# Guitar-Controller.net
KiCad netlist of a schematic drawn in EAGLE
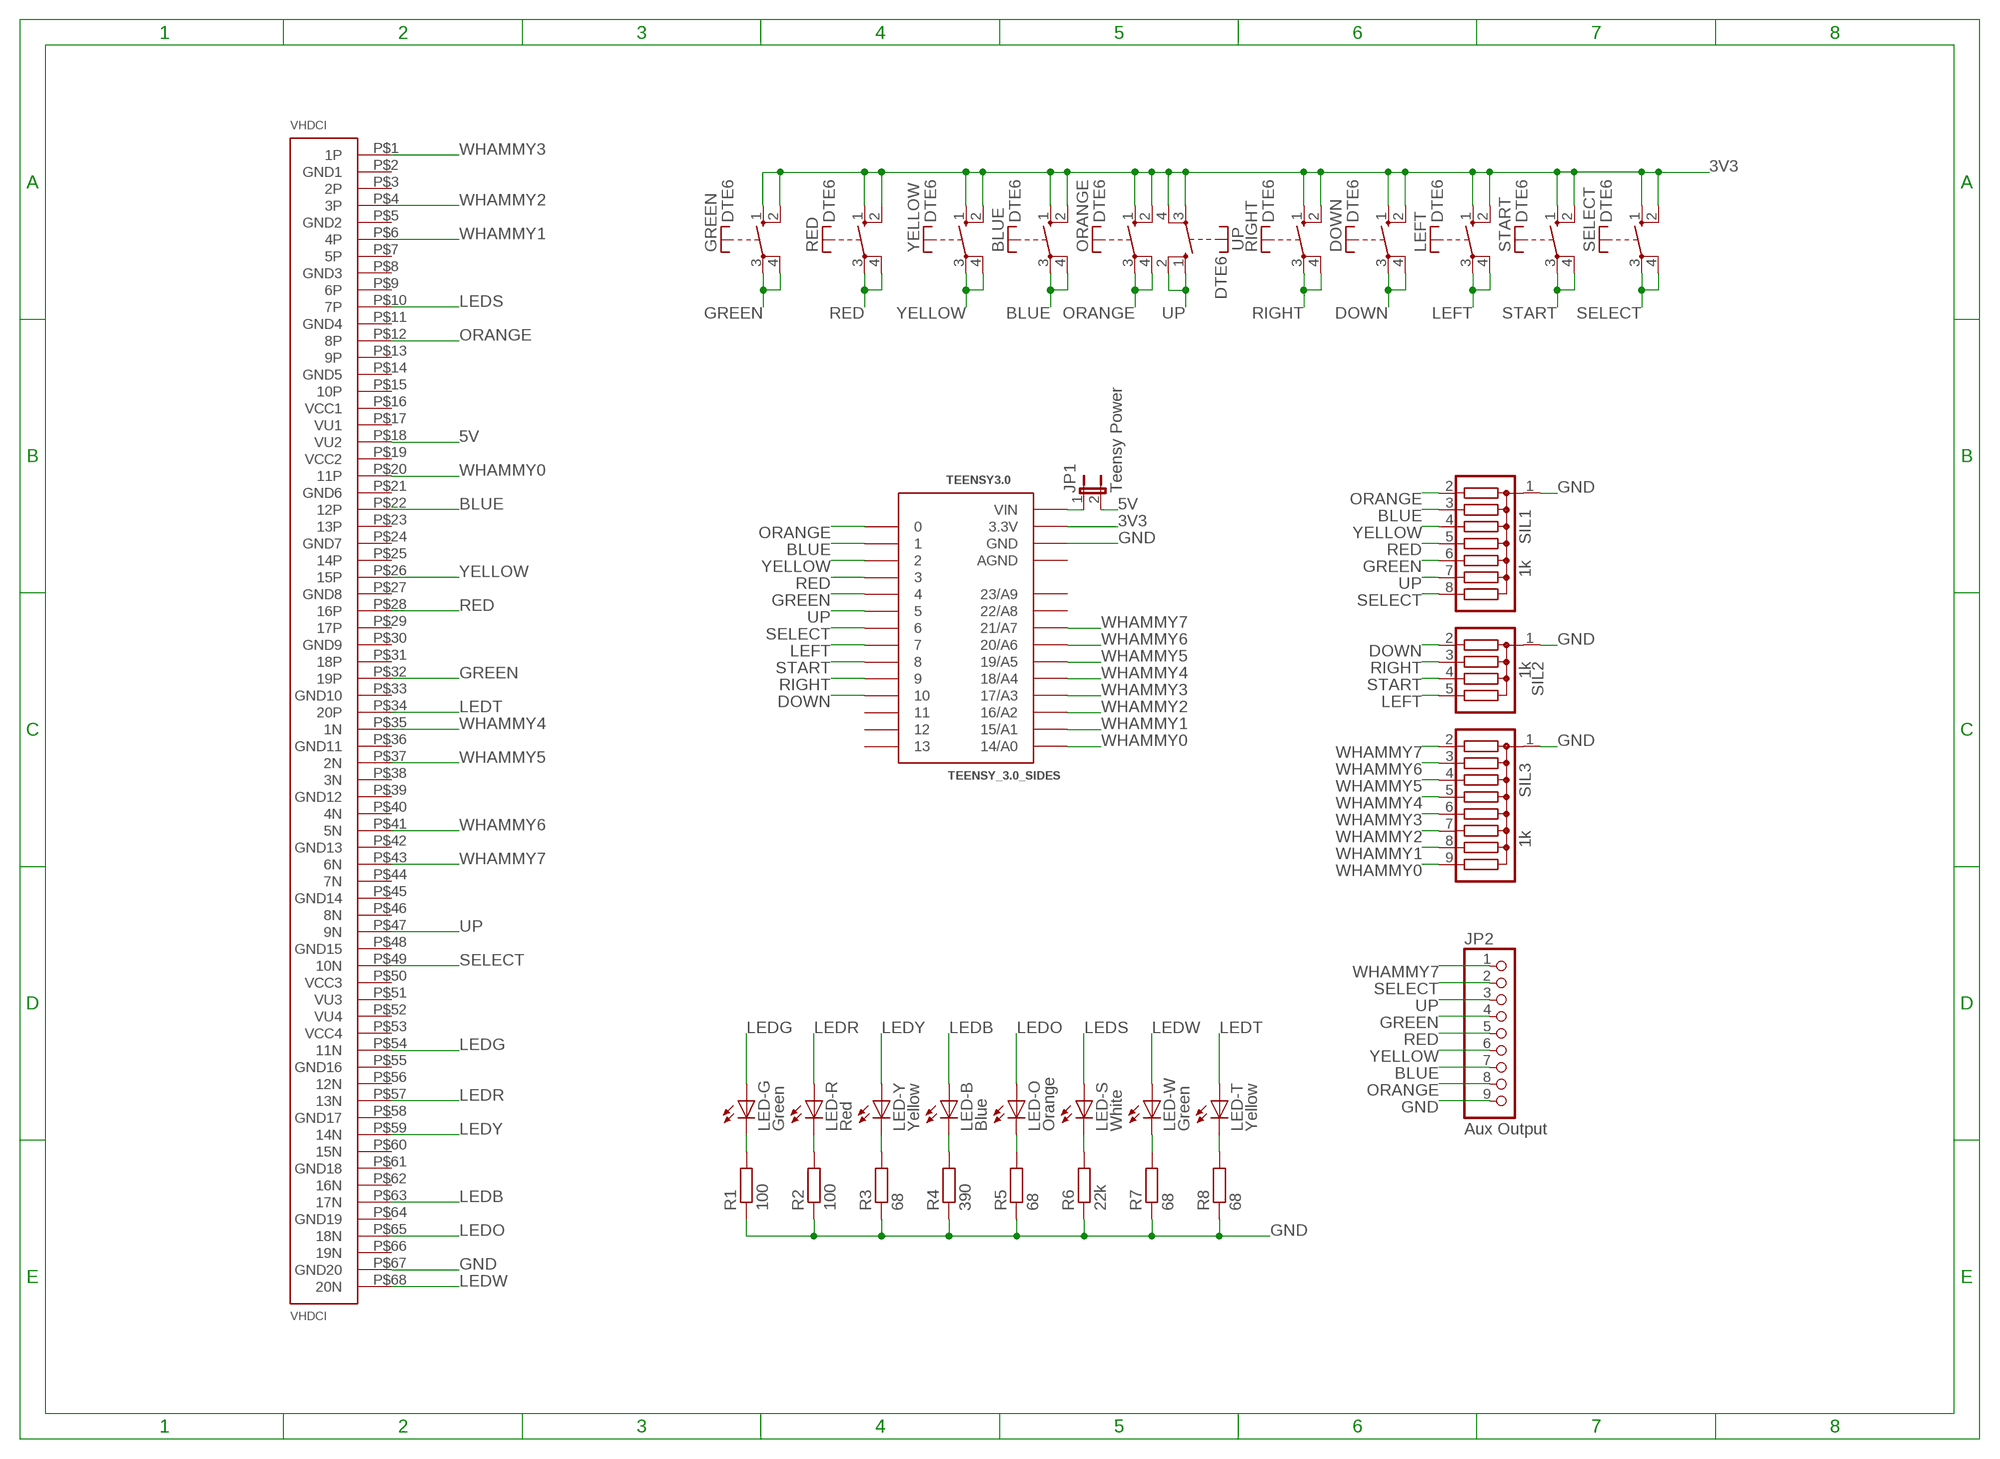
[diagram p0: schematic, sheet 1]

(export (version "E")
  (design (tool "Eeschema 10.0.6"))
  (components
    (comp (ref "BLUE")
      (value "DTE6")
      (footprint "eagle-import:DTE6")
      (libsource (lib "eagle-import") (part "DTE6"))
    )
    (comp (ref "DOWN")
      (value "DTE6")
      (footprint "eagle-import:DTE6")
      (libsource (lib "eagle-import") (part "DTE6"))
    )
    (comp (ref "GREEN")
      (value "DTE6")
      (footprint "eagle-import:DTE6")
      (libsource (lib "eagle-import") (part "DTE6"))
    )
    (comp (ref "JP1")
      (value "Teensy Power")
      (footprint "eagle-import:JP1")
      (libsource (lib "eagle-import") (part "JP1E"))
    )
    (comp (ref "JP2")
      (value "Aux Output")
      (footprint "eagle-import:1X09_90")
      (libsource (lib "eagle-import") (part "PINHD-1X9/90"))
    )
    (comp (ref "LED-B")
      (value "Blue")
      (footprint "eagle-import:LED2X5")
      (libsource (lib "eagle-import") (part "LEDSQR2X5"))
    )
    (comp (ref "LED-G")
      (value "Green")
      (footprint "eagle-import:LED2X5")
      (libsource (lib "eagle-import") (part "LEDSQR2X5"))
    )
    (comp (ref "LED-O")
      (value "Orange")
      (footprint "eagle-import:LED2X5")
      (libsource (lib "eagle-import") (part "LEDSQR2X5"))
    )
    (comp (ref "LED-R")
      (value "Red")
      (footprint "eagle-import:LED2X5")
      (libsource (lib "eagle-import") (part "LEDSQR2X5"))
    )
    (comp (ref "LED-S")
      (value "White")
      (footprint "eagle-import:LED5MM")
      (libsource (lib "eagle-import") (part "LED5MM"))
    )
    (comp (ref "LED-T")
      (value "Yellow")
      (footprint "eagle-import:LED3MM")
      (libsource (lib "eagle-import") (part "LED3MM"))
    )
    (comp (ref "LED-W")
      (value "Green")
      (footprint "eagle-import:LED3MM")
      (libsource (lib "eagle-import") (part "LED3MM"))
    )
    (comp (ref "LED-Y")
      (value "Yellow")
      (footprint "eagle-import:LED2X5")
      (libsource (lib "eagle-import") (part "LEDSQR2X5"))
    )
    (comp (ref "LEFT")
      (value "DTE6")
      (footprint "eagle-import:DTE6")
      (libsource (lib "eagle-import") (part "DTE6"))
    )
    (comp (ref "ORANGE")
      (value "DTE6")
      (footprint "eagle-import:DTE6")
      (libsource (lib "eagle-import") (part "DTE6"))
    )
    (comp (ref "R1")
      (value "100")
      (footprint "eagle-import:R0805")
      (libsource (lib "eagle-import") (part "R-EU_R0805"))
    )
    (comp (ref "R2")
      (value "100")
      (footprint "eagle-import:R0805")
      (libsource (lib "eagle-import") (part "R-EU_R0805"))
    )
    (comp (ref "R3")
      (value "68")
      (footprint "eagle-import:R0805")
      (libsource (lib "eagle-import") (part "R-EU_R0805"))
    )
    (comp (ref "R4")
      (value "390")
      (footprint "eagle-import:R0805")
      (libsource (lib "eagle-import") (part "R-EU_R0805"))
    )
    (comp (ref "R5")
      (value "68")
      (footprint "eagle-import:R0805")
      (libsource (lib "eagle-import") (part "R-EU_R0805"))
    )
    (comp (ref "R6")
      (value "22k")
      (footprint "eagle-import:R0805")
      (libsource (lib "eagle-import") (part "R-EU_R0805"))
    )
    (comp (ref "R7")
      (value "68")
      (footprint "eagle-import:R0805")
      (libsource (lib "eagle-import") (part "R-EU_R0805"))
    )
    (comp (ref "R8")
      (value "68")
      (footprint "eagle-import:R0805")
      (libsource (lib "eagle-import") (part "R-EU_R0805"))
    )
    (comp (ref "RED")
      (value "DTE6")
      (footprint "eagle-import:DTE6")
      (libsource (lib "eagle-import") (part "DTE6"))
    )
    (comp (ref "RIGHT")
      (value "DTE6")
      (footprint "eagle-import:DTE6")
      (libsource (lib "eagle-import") (part "DTE6"))
    )
    (comp (ref "SELECT")
      (value "DTE6")
      (footprint "eagle-import:DTE6")
      (libsource (lib "eagle-import") (part "DTE6"))
    )
    (comp (ref "SIL1")
      (value "1k")
      (footprint "eagle-import:SIL8")
      (libsource (lib "eagle-import") (part "G07R"))
    )
    (comp (ref "SIL2")
      (value "1k")
      (footprint "eagle-import:SIL5")
      (fields (field (name "OC_FARNELL") "unknown") (field (name "OC_NEWARK") "unknown"))
      (libsource (lib "eagle-import") (part "G04R"))
    )
    (comp (ref "SIL3")
      (value "1k")
      (footprint "eagle-import:SIL9")
      (libsource (lib "eagle-import") (part "G08R"))
    )
    (comp (ref "START")
      (value "DTE6")
      (footprint "eagle-import:DTE6")
      (libsource (lib "eagle-import") (part "DTE6"))
    )
    (comp (ref "TEENSY3.0")
      (value "TEENSY_3.0_SIDES")
      (footprint "eagle-import:TEENSY_3.0_SIDES")
      (libsource (lib "eagle-import") (part "TEENSY_3.0_SIDES"))
    )
    (comp (ref "UP")
      (value "DTE6")
      (footprint "eagle-import:DTE6")
      (libsource (lib "eagle-import") (part "DTE6"))
    )
    (comp (ref "VHDCI")
      (value "VHDCI-PLUG")
      (footprint "eagle-import:R-HI-008068-2")
      (libsource (lib "eagle-import") (part "VHDCI-PLUG"))
    )
    (comp (ref "YELLOW")
      (value "DTE6")
      (footprint "eagle-import:DTE6")
      (libsource (lib "eagle-import") (part "DTE6"))
    )
  )
  (nets
    (net (code "1") (name "/3V3") (class "Default")
      (node (ref "BLUE") (pin "1") (pinfunction "S_1") (pintype "passive"))
      (node (ref "BLUE") (pin "2") (pinfunction "S_2") (pintype "passive"))
      (node (ref "DOWN") (pin "1") (pinfunction "S_1") (pintype "passive"))
      (node (ref "DOWN") (pin "2") (pinfunction "S_2") (pintype "passive"))
      (node (ref "GREEN") (pin "1") (pinfunction "S_1") (pintype "passive"))
      (node (ref "GREEN") (pin "2") (pinfunction "S_2") (pintype "passive"))
      (node (ref "LEFT") (pin "1") (pinfunction "S_1") (pintype "passive"))
      (node (ref "LEFT") (pin "2") (pinfunction "S_2") (pintype "passive"))
      (node (ref "ORANGE") (pin "1") (pinfunction "S_1") (pintype "passive"))
      (node (ref "ORANGE") (pin "2") (pinfunction "S_2") (pintype "passive"))
      (node (ref "RED") (pin "1") (pinfunction "S_1") (pintype "passive"))
      (node (ref "RED") (pin "2") (pinfunction "S_2") (pintype "passive"))
      (node (ref "RIGHT") (pin "1") (pinfunction "S_1") (pintype "passive"))
      (node (ref "RIGHT") (pin "2") (pinfunction "S_2") (pintype "passive"))
      (node (ref "SELECT") (pin "1") (pinfunction "S_1") (pintype "passive"))
      (node (ref "SELECT") (pin "2") (pinfunction "S_2") (pintype "passive"))
      (node (ref "START") (pin "1") (pinfunction "S_1") (pintype "passive"))
      (node (ref "START") (pin "2") (pinfunction "S_2") (pintype "passive"))
      (node (ref "TEENSY3.0") (pin "3.3V") (pinfunction "3.3V_3.3V") (pintype "power_in"))
      (node (ref "UP") (pin "3") (pinfunction "P_3") (pintype "passive"))
      (node (ref "UP") (pin "4") (pinfunction "P_4") (pintype "passive"))
      (node (ref "YELLOW") (pin "1") (pinfunction "S_1") (pintype "passive"))
      (node (ref "YELLOW") (pin "2") (pinfunction "S_2") (pintype "passive"))
    )
    (net (code "2") (name "/5V") (class "Default")
      (node (ref "JP1") (pin "2") (pinfunction "2_2") (pintype "passive"))
      (node (ref "VHDCI") (pin "P$18") (pinfunction "VU2_P$18") (pintype "bidirectional"))
    )
    (net (code "3") (name "/AGND") (class "Default")
      (node (ref "TEENSY3.0") (pin "AGND") (pinfunction "AGND_AGND") (pintype "power_in"))
    )
    (net (code "4") (name "/BLUE") (class "Default")
      (node (ref "BLUE") (pin "3") (pinfunction "P_3") (pintype "passive"))
      (node (ref "BLUE") (pin "4") (pinfunction "P_4") (pintype "passive"))
      (node (ref "JP2") (pin "7") (pinfunction "7_7") (pintype "passive"))
      (node (ref "SIL1") (pin "3") (pinfunction "3_3") (pintype "passive"))
      (node (ref "TEENSY3.0") (pin "1") (pinfunction "1_1") (pintype "bidirectional"))
      (node (ref "VHDCI") (pin "P$22") (pinfunction "12P_P$22") (pintype "bidirectional"))
    )
    (net (code "5") (name "/DOWN") (class "Default")
      (node (ref "DOWN") (pin "3") (pinfunction "P_3") (pintype "passive"))
      (node (ref "DOWN") (pin "4") (pinfunction "P_4") (pintype "passive"))
      (node (ref "SIL2") (pin "2") (pinfunction "2_2") (pintype "passive"))
      (node (ref "TEENSY3.0") (pin "10") (pinfunction "10_10") (pintype "bidirectional"))
    )
    (net (code "6") (name "/GND") (class "Default")
      (node (ref "JP2") (pin "9") (pinfunction "9_9") (pintype "passive"))
      (node (ref "R1") (pin "1") (pinfunction "1_1") (pintype "passive"))
      (node (ref "R2") (pin "1") (pinfunction "1_1") (pintype "passive"))
      (node (ref "R3") (pin "1") (pinfunction "1_1") (pintype "passive"))
      (node (ref "R4") (pin "1") (pinfunction "1_1") (pintype "passive"))
      (node (ref "R5") (pin "1") (pinfunction "1_1") (pintype "passive"))
      (node (ref "R6") (pin "1") (pinfunction "1_1") (pintype "passive"))
      (node (ref "R7") (pin "1") (pinfunction "1_1") (pintype "passive"))
      (node (ref "R8") (pin "1") (pinfunction "1_1") (pintype "passive"))
      (node (ref "SIL1") (pin "1") (pinfunction "1_1") (pintype "passive"))
      (node (ref "SIL2") (pin "1") (pinfunction "1_1") (pintype "passive"))
      (node (ref "SIL3") (pin "1") (pinfunction "1_1") (pintype "passive"))
      (node (ref "TEENSY3.0") (pin "GND") (pinfunction "GND_GND") (pintype "power_in"))
      (node (ref "VHDCI") (pin "P$67") (pinfunction "GND20_P$67") (pintype "bidirectional"))
    )
    (net (code "7") (name "/GREEN") (class "Default")
      (node (ref "GREEN") (pin "3") (pinfunction "P_3") (pintype "passive"))
      (node (ref "GREEN") (pin "4") (pinfunction "P_4") (pintype "passive"))
      (node (ref "JP2") (pin "4") (pinfunction "4_4") (pintype "passive"))
      (node (ref "SIL1") (pin "6") (pinfunction "6_6") (pintype "passive"))
      (node (ref "TEENSY3.0") (pin "4") (pinfunction "4_4") (pintype "bidirectional"))
      (node (ref "VHDCI") (pin "P$32") (pinfunction "19P_P$32") (pintype "bidirectional"))
    )
    (net (code "8") (name "/LEDB") (class "Default")
      (node (ref "LED-B") (pin "A") (pinfunction "A_A") (pintype "passive"))
      (node (ref "VHDCI") (pin "P$63") (pinfunction "17N_P$63") (pintype "bidirectional"))
    )
    (net (code "9") (name "/LEDG") (class "Default")
      (node (ref "LED-G") (pin "A") (pinfunction "A_A") (pintype "passive"))
      (node (ref "VHDCI") (pin "P$54") (pinfunction "11N_P$54") (pintype "bidirectional"))
    )
    (net (code "10") (name "/LEDO") (class "Default")
      (node (ref "LED-O") (pin "A") (pinfunction "A_A") (pintype "passive"))
      (node (ref "VHDCI") (pin "P$65") (pinfunction "18N_P$65") (pintype "bidirectional"))
    )
    (net (code "11") (name "/LEDR") (class "Default")
      (node (ref "LED-R") (pin "A") (pinfunction "A_A") (pintype "passive"))
      (node (ref "VHDCI") (pin "P$57") (pinfunction "13N_P$57") (pintype "bidirectional"))
    )
    (net (code "12") (name "/LEDS") (class "Default")
      (node (ref "LED-S") (pin "A") (pinfunction "A_A") (pintype "passive"))
      (node (ref "VHDCI") (pin "P$10") (pinfunction "7P_P$10") (pintype "bidirectional"))
    )
    (net (code "13") (name "/LEDT") (class "Default")
      (node (ref "LED-T") (pin "A") (pinfunction "A_A") (pintype "passive"))
      (node (ref "VHDCI") (pin "P$34") (pinfunction "20P_P$34") (pintype "bidirectional"))
    )
    (net (code "14") (name "/LEDW") (class "Default")
      (node (ref "LED-W") (pin "A") (pinfunction "A_A") (pintype "passive"))
      (node (ref "VHDCI") (pin "P$68") (pinfunction "20N_P$68") (pintype "bidirectional"))
    )
    (net (code "15") (name "/LEDY") (class "Default")
      (node (ref "LED-Y") (pin "A") (pinfunction "A_A") (pintype "passive"))
      (node (ref "VHDCI") (pin "P$59") (pinfunction "14N_P$59") (pintype "bidirectional"))
    )
    (net (code "16") (name "/LEFT") (class "Default")
      (node (ref "LEFT") (pin "3") (pinfunction "P_3") (pintype "passive"))
      (node (ref "LEFT") (pin "4") (pinfunction "P_4") (pintype "passive"))
      (node (ref "SIL2") (pin "5") (pinfunction "5_5") (pintype "passive"))
      (node (ref "TEENSY3.0") (pin "7") (pinfunction "7_7") (pintype "bidirectional"))
    )
    (net (code "17") (name "/ORANGE") (class "Default")
      (node (ref "JP2") (pin "8") (pinfunction "8_8") (pintype "passive"))
      (node (ref "ORANGE") (pin "3") (pinfunction "P_3") (pintype "passive"))
      (node (ref "ORANGE") (pin "4") (pinfunction "P_4") (pintype "passive"))
      (node (ref "SIL1") (pin "2") (pinfunction "2_2") (pintype "passive"))
      (node (ref "TEENSY3.0") (pin "0") (pinfunction "0_0") (pintype "bidirectional"))
      (node (ref "VHDCI") (pin "P$12") (pinfunction "8P_P$12") (pintype "bidirectional"))
    )
    (net (code "18") (name "/RED") (class "Default")
      (node (ref "JP2") (pin "5") (pinfunction "5_5") (pintype "passive"))
      (node (ref "RED") (pin "3") (pinfunction "P_3") (pintype "passive"))
      (node (ref "RED") (pin "4") (pinfunction "P_4") (pintype "passive"))
      (node (ref "SIL1") (pin "5") (pinfunction "5_5") (pintype "passive"))
      (node (ref "TEENSY3.0") (pin "3") (pinfunction "3_3") (pintype "bidirectional"))
      (node (ref "VHDCI") (pin "P$28") (pinfunction "16P_P$28") (pintype "bidirectional"))
    )
    (net (code "19") (name "/RIGHT") (class "Default")
      (node (ref "RIGHT") (pin "3") (pinfunction "P_3") (pintype "passive"))
      (node (ref "RIGHT") (pin "4") (pinfunction "P_4") (pintype "passive"))
      (node (ref "SIL2") (pin "3") (pinfunction "3_3") (pintype "passive"))
      (node (ref "TEENSY3.0") (pin "9") (pinfunction "9_9") (pintype "bidirectional"))
    )
    (net (code "20") (name "/SELECT") (class "Default")
      (node (ref "JP2") (pin "2") (pinfunction "2_2") (pintype "passive"))
      (node (ref "SELECT") (pin "3") (pinfunction "P_3") (pintype "passive"))
      (node (ref "SELECT") (pin "4") (pinfunction "P_4") (pintype "passive"))
      (node (ref "SIL1") (pin "8") (pinfunction "8_8") (pintype "passive"))
      (node (ref "TEENSY3.0") (pin "6") (pinfunction "6_6") (pintype "bidirectional"))
      (node (ref "VHDCI") (pin "P$49") (pinfunction "10N_P$49") (pintype "bidirectional"))
    )
    (net (code "21") (name "/START") (class "Default")
      (node (ref "SIL2") (pin "4") (pinfunction "4_4") (pintype "passive"))
      (node (ref "START") (pin "3") (pinfunction "P_3") (pintype "passive"))
      (node (ref "START") (pin "4") (pinfunction "P_4") (pintype "passive"))
      (node (ref "TEENSY3.0") (pin "8") (pinfunction "8_8") (pintype "bidirectional"))
    )
    (net (code "22") (name "/UP") (class "Default")
      (node (ref "JP2") (pin "3") (pinfunction "3_3") (pintype "passive"))
      (node (ref "SIL1") (pin "7") (pinfunction "7_7") (pintype "passive"))
      (node (ref "TEENSY3.0") (pin "5") (pinfunction "5_5") (pintype "bidirectional"))
      (node (ref "UP") (pin "1") (pinfunction "S_1") (pintype "passive"))
      (node (ref "UP") (pin "2") (pinfunction "S_2") (pintype "passive"))
      (node (ref "VHDCI") (pin "P$47") (pinfunction "9N_P$47") (pintype "bidirectional"))
    )
    (net (code "23") (name "/WHAMMY0") (class "Default")
      (node (ref "SIL3") (pin "9") (pinfunction "9_9") (pintype "passive"))
      (node (ref "TEENSY3.0") (pin "14/A0") (pinfunction "14/A0_14/A0") (pintype "bidirectional"))
      (node (ref "VHDCI") (pin "P$20") (pinfunction "11P_P$20") (pintype "bidirectional"))
    )
    (net (code "24") (name "/WHAMMY1") (class "Default")
      (node (ref "SIL3") (pin "8") (pinfunction "8_8") (pintype "passive"))
      (node (ref "TEENSY3.0") (pin "15/A1") (pinfunction "15/A1_15/A1") (pintype "bidirectional"))
      (node (ref "VHDCI") (pin "P$6") (pinfunction "4P_P$6") (pintype "bidirectional"))
    )
    (net (code "25") (name "/WHAMMY2") (class "Default")
      (node (ref "SIL3") (pin "7") (pinfunction "7_7") (pintype "passive"))
      (node (ref "TEENSY3.0") (pin "16/A2") (pinfunction "16/A2_16/A2") (pintype "bidirectional"))
      (node (ref "VHDCI") (pin "P$4") (pinfunction "3P_P$4") (pintype "bidirectional"))
    )
    (net (code "26") (name "/WHAMMY3") (class "Default")
      (node (ref "SIL3") (pin "6") (pinfunction "6_6") (pintype "passive"))
      (node (ref "TEENSY3.0") (pin "17/A3") (pinfunction "17/A3_17/A3") (pintype "bidirectional"))
      (node (ref "VHDCI") (pin "P$1") (pinfunction "1P_P$1") (pintype "bidirectional"))
    )
    (net (code "27") (name "/WHAMMY4") (class "Default")
      (node (ref "SIL3") (pin "5") (pinfunction "5_5") (pintype "passive"))
      (node (ref "TEENSY3.0") (pin "18/A4") (pinfunction "18/A4_18/A4") (pintype "bidirectional"))
      (node (ref "VHDCI") (pin "P$35") (pinfunction "1N_P$35") (pintype "bidirectional"))
    )
    (net (code "28") (name "/WHAMMY5") (class "Default")
      (node (ref "SIL3") (pin "4") (pinfunction "4_4") (pintype "passive"))
      (node (ref "TEENSY3.0") (pin "19/A5") (pinfunction "19/A5_19/A5") (pintype "bidirectional"))
      (node (ref "VHDCI") (pin "P$37") (pinfunction "2N_P$37") (pintype "bidirectional"))
    )
    (net (code "29") (name "/WHAMMY6") (class "Default")
      (node (ref "SIL3") (pin "3") (pinfunction "3_3") (pintype "passive"))
      (node (ref "TEENSY3.0") (pin "20/A6") (pinfunction "20/A6_20/A6") (pintype "bidirectional"))
      (node (ref "VHDCI") (pin "P$41") (pinfunction "5N_P$41") (pintype "bidirectional"))
    )
    (net (code "30") (name "/WHAMMY7") (class "Default")
      (node (ref "JP2") (pin "1") (pinfunction "1_1") (pintype "passive"))
      (node (ref "SIL3") (pin "2") (pinfunction "2_2") (pintype "passive"))
      (node (ref "TEENSY3.0") (pin "21/A7") (pinfunction "21/A7_21/A7") (pintype "bidirectional"))
      (node (ref "VHDCI") (pin "P$43") (pinfunction "6N_P$43") (pintype "bidirectional"))
    )
    (net (code "31") (name "/YELLOW") (class "Default")
      (node (ref "JP2") (pin "6") (pinfunction "6_6") (pintype "passive"))
      (node (ref "SIL1") (pin "4") (pinfunction "4_4") (pintype "passive"))
      (node (ref "TEENSY3.0") (pin "2") (pinfunction "2_2") (pintype "bidirectional"))
      (node (ref "VHDCI") (pin "P$26") (pinfunction "15P_P$26") (pintype "bidirectional"))
      (node (ref "YELLOW") (pin "3") (pinfunction "P_3") (pintype "passive"))
      (node (ref "YELLOW") (pin "4") (pinfunction "P_4") (pintype "passive"))
    )
    (net (code "32") (name "Net-(JP1-Pad1)") (class "Default")
      (node (ref "JP1") (pin "1") (pinfunction "1_1") (pintype "passive"))
      (node (ref "TEENSY3.0") (pin "VIN") (pinfunction "VIN_VIN") (pintype "power_in"))
    )
    (net (code "33") (name "Net-(LED-B-C)") (class "Default")
      (node (ref "LED-B") (pin "K") (pinfunction "C_K") (pintype "passive"))
      (node (ref "R4") (pin "2") (pinfunction "2_2") (pintype "passive"))
    )
    (net (code "34") (name "Net-(LED-G-C)") (class "Default")
      (node (ref "LED-G") (pin "K") (pinfunction "C_K") (pintype "passive"))
      (node (ref "R1") (pin "2") (pinfunction "2_2") (pintype "passive"))
    )
    (net (code "35") (name "Net-(LED-O-C)") (class "Default")
      (node (ref "LED-O") (pin "K") (pinfunction "C_K") (pintype "passive"))
      (node (ref "R5") (pin "2") (pinfunction "2_2") (pintype "passive"))
    )
    (net (code "36") (name "Net-(LED-R-C)") (class "Default")
      (node (ref "LED-R") (pin "K") (pinfunction "C_K") (pintype "passive"))
      (node (ref "R2") (pin "2") (pinfunction "2_2") (pintype "passive"))
    )
    (net (code "37") (name "Net-(LED-S-C)") (class "Default")
      (node (ref "LED-S") (pin "K") (pinfunction "C_K") (pintype "passive"))
      (node (ref "R6") (pin "2") (pinfunction "2_2") (pintype "passive"))
    )
    (net (code "38") (name "Net-(LED-T-C)") (class "Default")
      (node (ref "LED-T") (pin "K") (pinfunction "C_K") (pintype "passive"))
      (node (ref "R8") (pin "2") (pinfunction "2_2") (pintype "passive"))
    )
    (net (code "39") (name "Net-(LED-W-C)") (class "Default")
      (node (ref "LED-W") (pin "K") (pinfunction "C_K") (pintype "passive"))
      (node (ref "R7") (pin "2") (pinfunction "2_2") (pintype "passive"))
    )
    (net (code "40") (name "Net-(LED-Y-C)") (class "Default")
      (node (ref "LED-Y") (pin "K") (pinfunction "C_K") (pintype "passive"))
      (node (ref "R3") (pin "2") (pinfunction "2_2") (pintype "passive"))
    )
    (net (code "41") (name "unconnected-(TEENSY3.0-Pad11)") (class "Default")
      (node (ref "TEENSY3.0") (pin "11") (pinfunction "11_11") (pintype "bidirectional"))
    )
    (net (code "42") (name "unconnected-(TEENSY3.0-Pad12)") (class "Default")
      (node (ref "TEENSY3.0") (pin "12") (pinfunction "12_12") (pintype "bidirectional"))
    )
    (net (code "43") (name "unconnected-(TEENSY3.0-Pad13)") (class "Default")
      (node (ref "TEENSY3.0") (pin "13") (pinfunction "13_13") (pintype "bidirectional"))
    )
    (net (code "44") (name "unconnected-(TEENSY3.0-Pad22{slash}A8)") (class "Default")
      (node (ref "TEENSY3.0") (pin "22/A8") (pinfunction "22/A8_22/A8") (pintype "bidirectional"))
    )
    (net (code "45") (name "unconnected-(TEENSY3.0-Pad23{slash}A9)") (class "Default")
      (node (ref "TEENSY3.0") (pin "23/A9") (pinfunction "23/A9_23/A9") (pintype "bidirectional"))
    )
    (net (code "46") (name "unconnected-(VHDCI-2P-PadP$3)") (class "Default")
      (node (ref "VHDCI") (pin "P$3") (pinfunction "2P_P$3") (pintype "bidirectional"))
    )
    (net (code "47") (name "unconnected-(VHDCI-3N-PadP$38)") (class "Default")
      (node (ref "VHDCI") (pin "P$38") (pinfunction "3N_P$38") (pintype "bidirectional"))
    )
    (net (code "48") (name "unconnected-(VHDCI-4N-PadP$40)") (class "Default")
      (node (ref "VHDCI") (pin "P$40") (pinfunction "4N_P$40") (pintype "bidirectional"))
    )
    (net (code "49") (name "unconnected-(VHDCI-5P-PadP$7)") (class "Default")
      (node (ref "VHDCI") (pin "P$7") (pinfunction "5P_P$7") (pintype "bidirectional"))
    )
    (net (code "50") (name "unconnected-(VHDCI-6P-PadP$9)") (class "Default")
      (node (ref "VHDCI") (pin "P$9") (pinfunction "6P_P$9") (pintype "bidirectional"))
    )
    (net (code "51") (name "unconnected-(VHDCI-7N-PadP$44)") (class "Default")
      (node (ref "VHDCI") (pin "P$44") (pinfunction "7N_P$44") (pintype "bidirectional"))
    )
    (net (code "52") (name "unconnected-(VHDCI-8N-PadP$46)") (class "Default")
      (node (ref "VHDCI") (pin "P$46") (pinfunction "8N_P$46") (pintype "bidirectional"))
    )
    (net (code "53") (name "unconnected-(VHDCI-9P-PadP$13)") (class "Default")
      (node (ref "VHDCI") (pin "P$13") (pinfunction "9P_P$13") (pintype "bidirectional"))
    )
    (net (code "54") (name "unconnected-(VHDCI-10P-PadP$15)") (class "Default")
      (node (ref "VHDCI") (pin "P$15") (pinfunction "10P_P$15") (pintype "bidirectional"))
    )
    (net (code "55") (name "unconnected-(VHDCI-12N-PadP$56)") (class "Default")
      (node (ref "VHDCI") (pin "P$56") (pinfunction "12N_P$56") (pintype "bidirectional"))
    )
    (net (code "56") (name "unconnected-(VHDCI-13P-PadP$23)") (class "Default")
      (node (ref "VHDCI") (pin "P$23") (pinfunction "13P_P$23") (pintype "bidirectional"))
    )
    (net (code "57") (name "unconnected-(VHDCI-14P-PadP$25)") (class "Default")
      (node (ref "VHDCI") (pin "P$25") (pinfunction "14P_P$25") (pintype "bidirectional"))
    )
    (net (code "58") (name "unconnected-(VHDCI-15N-PadP$60)") (class "Default")
      (node (ref "VHDCI") (pin "P$60") (pinfunction "15N_P$60") (pintype "bidirectional"))
    )
    (net (code "59") (name "unconnected-(VHDCI-16N-PadP$62)") (class "Default")
      (node (ref "VHDCI") (pin "P$62") (pinfunction "16N_P$62") (pintype "bidirectional"))
    )
    (net (code "60") (name "unconnected-(VHDCI-17P-PadP$29)") (class "Default")
      (node (ref "VHDCI") (pin "P$29") (pinfunction "17P_P$29") (pintype "bidirectional"))
    )
    (net (code "61") (name "unconnected-(VHDCI-18P-PadP$31)") (class "Default")
      (node (ref "VHDCI") (pin "P$31") (pinfunction "18P_P$31") (pintype "bidirectional"))
    )
    (net (code "62") (name "unconnected-(VHDCI-19N-PadP$66)") (class "Default")
      (node (ref "VHDCI") (pin "P$66") (pinfunction "19N_P$66") (pintype "bidirectional"))
    )
    (net (code "63") (name "unconnected-(VHDCI-GND1-PadP$2)") (class "Default")
      (node (ref "VHDCI") (pin "P$2") (pinfunction "GND1_P$2") (pintype "bidirectional"))
    )
    (net (code "64") (name "unconnected-(VHDCI-GND2-PadP$5)") (class "Default")
      (node (ref "VHDCI") (pin "P$5") (pinfunction "GND2_P$5") (pintype "bidirectional"))
    )
    (net (code "65") (name "unconnected-(VHDCI-GND3-PadP$8)") (class "Default")
      (node (ref "VHDCI") (pin "P$8") (pinfunction "GND3_P$8") (pintype "bidirectional"))
    )
    (net (code "66") (name "unconnected-(VHDCI-GND4-PadP$11)") (class "Default")
      (node (ref "VHDCI") (pin "P$11") (pinfunction "GND4_P$11") (pintype "bidirectional"))
    )
    (net (code "67") (name "unconnected-(VHDCI-GND5-PadP$14)") (class "Default")
      (node (ref "VHDCI") (pin "P$14") (pinfunction "GND5_P$14") (pintype "bidirectional"))
    )
    (net (code "68") (name "unconnected-(VHDCI-GND6-PadP$21)") (class "Default")
      (node (ref "VHDCI") (pin "P$21") (pinfunction "GND6_P$21") (pintype "bidirectional"))
    )
    (net (code "69") (name "unconnected-(VHDCI-GND7-PadP$24)") (class "Default")
      (node (ref "VHDCI") (pin "P$24") (pinfunction "GND7_P$24") (pintype "bidirectional"))
    )
    (net (code "70") (name "unconnected-(VHDCI-GND8-PadP$27)") (class "Default")
      (node (ref "VHDCI") (pin "P$27") (pinfunction "GND8_P$27") (pintype "bidirectional"))
    )
    (net (code "71") (name "unconnected-(VHDCI-GND9-PadP$30)") (class "Default")
      (node (ref "VHDCI") (pin "P$30") (pinfunction "GND9_P$30") (pintype "bidirectional"))
    )
    (net (code "72") (name "unconnected-(VHDCI-GND10-PadP$33)") (class "Default")
      (node (ref "VHDCI") (pin "P$33") (pinfunction "GND10_P$33") (pintype "bidirectional"))
    )
    (net (code "73") (name "unconnected-(VHDCI-GND11-PadP$36)") (class "Default")
      (node (ref "VHDCI") (pin "P$36") (pinfunction "GND11_P$36") (pintype "bidirectional"))
    )
    (net (code "74") (name "unconnected-(VHDCI-GND12-PadP$39)") (class "Default")
      (node (ref "VHDCI") (pin "P$39") (pinfunction "GND12_P$39") (pintype "bidirectional"))
    )
    (net (code "75") (name "unconnected-(VHDCI-GND13-PadP$42)") (class "Default")
      (node (ref "VHDCI") (pin "P$42") (pinfunction "GND13_P$42") (pintype "bidirectional"))
    )
    (net (code "76") (name "unconnected-(VHDCI-GND14-PadP$45)") (class "Default")
      (node (ref "VHDCI") (pin "P$45") (pinfunction "GND14_P$45") (pintype "bidirectional"))
    )
    (net (code "77") (name "unconnected-(VHDCI-GND15-PadP$48)") (class "Default")
      (node (ref "VHDCI") (pin "P$48") (pinfunction "GND15_P$48") (pintype "bidirectional"))
    )
    (net (code "78") (name "unconnected-(VHDCI-GND16-PadP$55)") (class "Default")
      (node (ref "VHDCI") (pin "P$55") (pinfunction "GND16_P$55") (pintype "bidirectional"))
    )
    (net (code "79") (name "unconnected-(VHDCI-GND17-PadP$58)") (class "Default")
      (node (ref "VHDCI") (pin "P$58") (pinfunction "GND17_P$58") (pintype "bidirectional"))
    )
    (net (code "80") (name "unconnected-(VHDCI-GND18-PadP$61)") (class "Default")
      (node (ref "VHDCI") (pin "P$61") (pinfunction "GND18_P$61") (pintype "bidirectional"))
    )
    (net (code "81") (name "unconnected-(VHDCI-GND19-PadP$64)") (class "Default")
      (node (ref "VHDCI") (pin "P$64") (pinfunction "GND19_P$64") (pintype "bidirectional"))
    )
    (net (code "82") (name "unconnected-(VHDCI-VCC1-PadP$16)") (class "Default")
      (node (ref "VHDCI") (pin "P$16") (pinfunction "VCC1_P$16") (pintype "bidirectional"))
    )
    (net (code "83") (name "unconnected-(VHDCI-VCC2-PadP$19)") (class "Default")
      (node (ref "VHDCI") (pin "P$19") (pinfunction "VCC2_P$19") (pintype "bidirectional"))
    )
    (net (code "84") (name "unconnected-(VHDCI-VCC3-PadP$50)") (class "Default")
      (node (ref "VHDCI") (pin "P$50") (pinfunction "VCC3_P$50") (pintype "bidirectional"))
    )
    (net (code "85") (name "unconnected-(VHDCI-VCC4-PadP$53)") (class "Default")
      (node (ref "VHDCI") (pin "P$53") (pinfunction "VCC4_P$53") (pintype "bidirectional"))
    )
    (net (code "86") (name "unconnected-(VHDCI-VU1-PadP$17)") (class "Default")
      (node (ref "VHDCI") (pin "P$17") (pinfunction "VU1_P$17") (pintype "bidirectional"))
    )
    (net (code "87") (name "unconnected-(VHDCI-VU3-PadP$51)") (class "Default")
      (node (ref "VHDCI") (pin "P$51") (pinfunction "VU3_P$51") (pintype "bidirectional"))
    )
    (net (code "88") (name "unconnected-(VHDCI-VU4-PadP$52)") (class "Default")
      (node (ref "VHDCI") (pin "P$52") (pinfunction "VU4_P$52") (pintype "bidirectional"))
    )
  )
)
